# PR2387_Monitor.net
KiCad netlist of a schematic drawn in Altium Designer
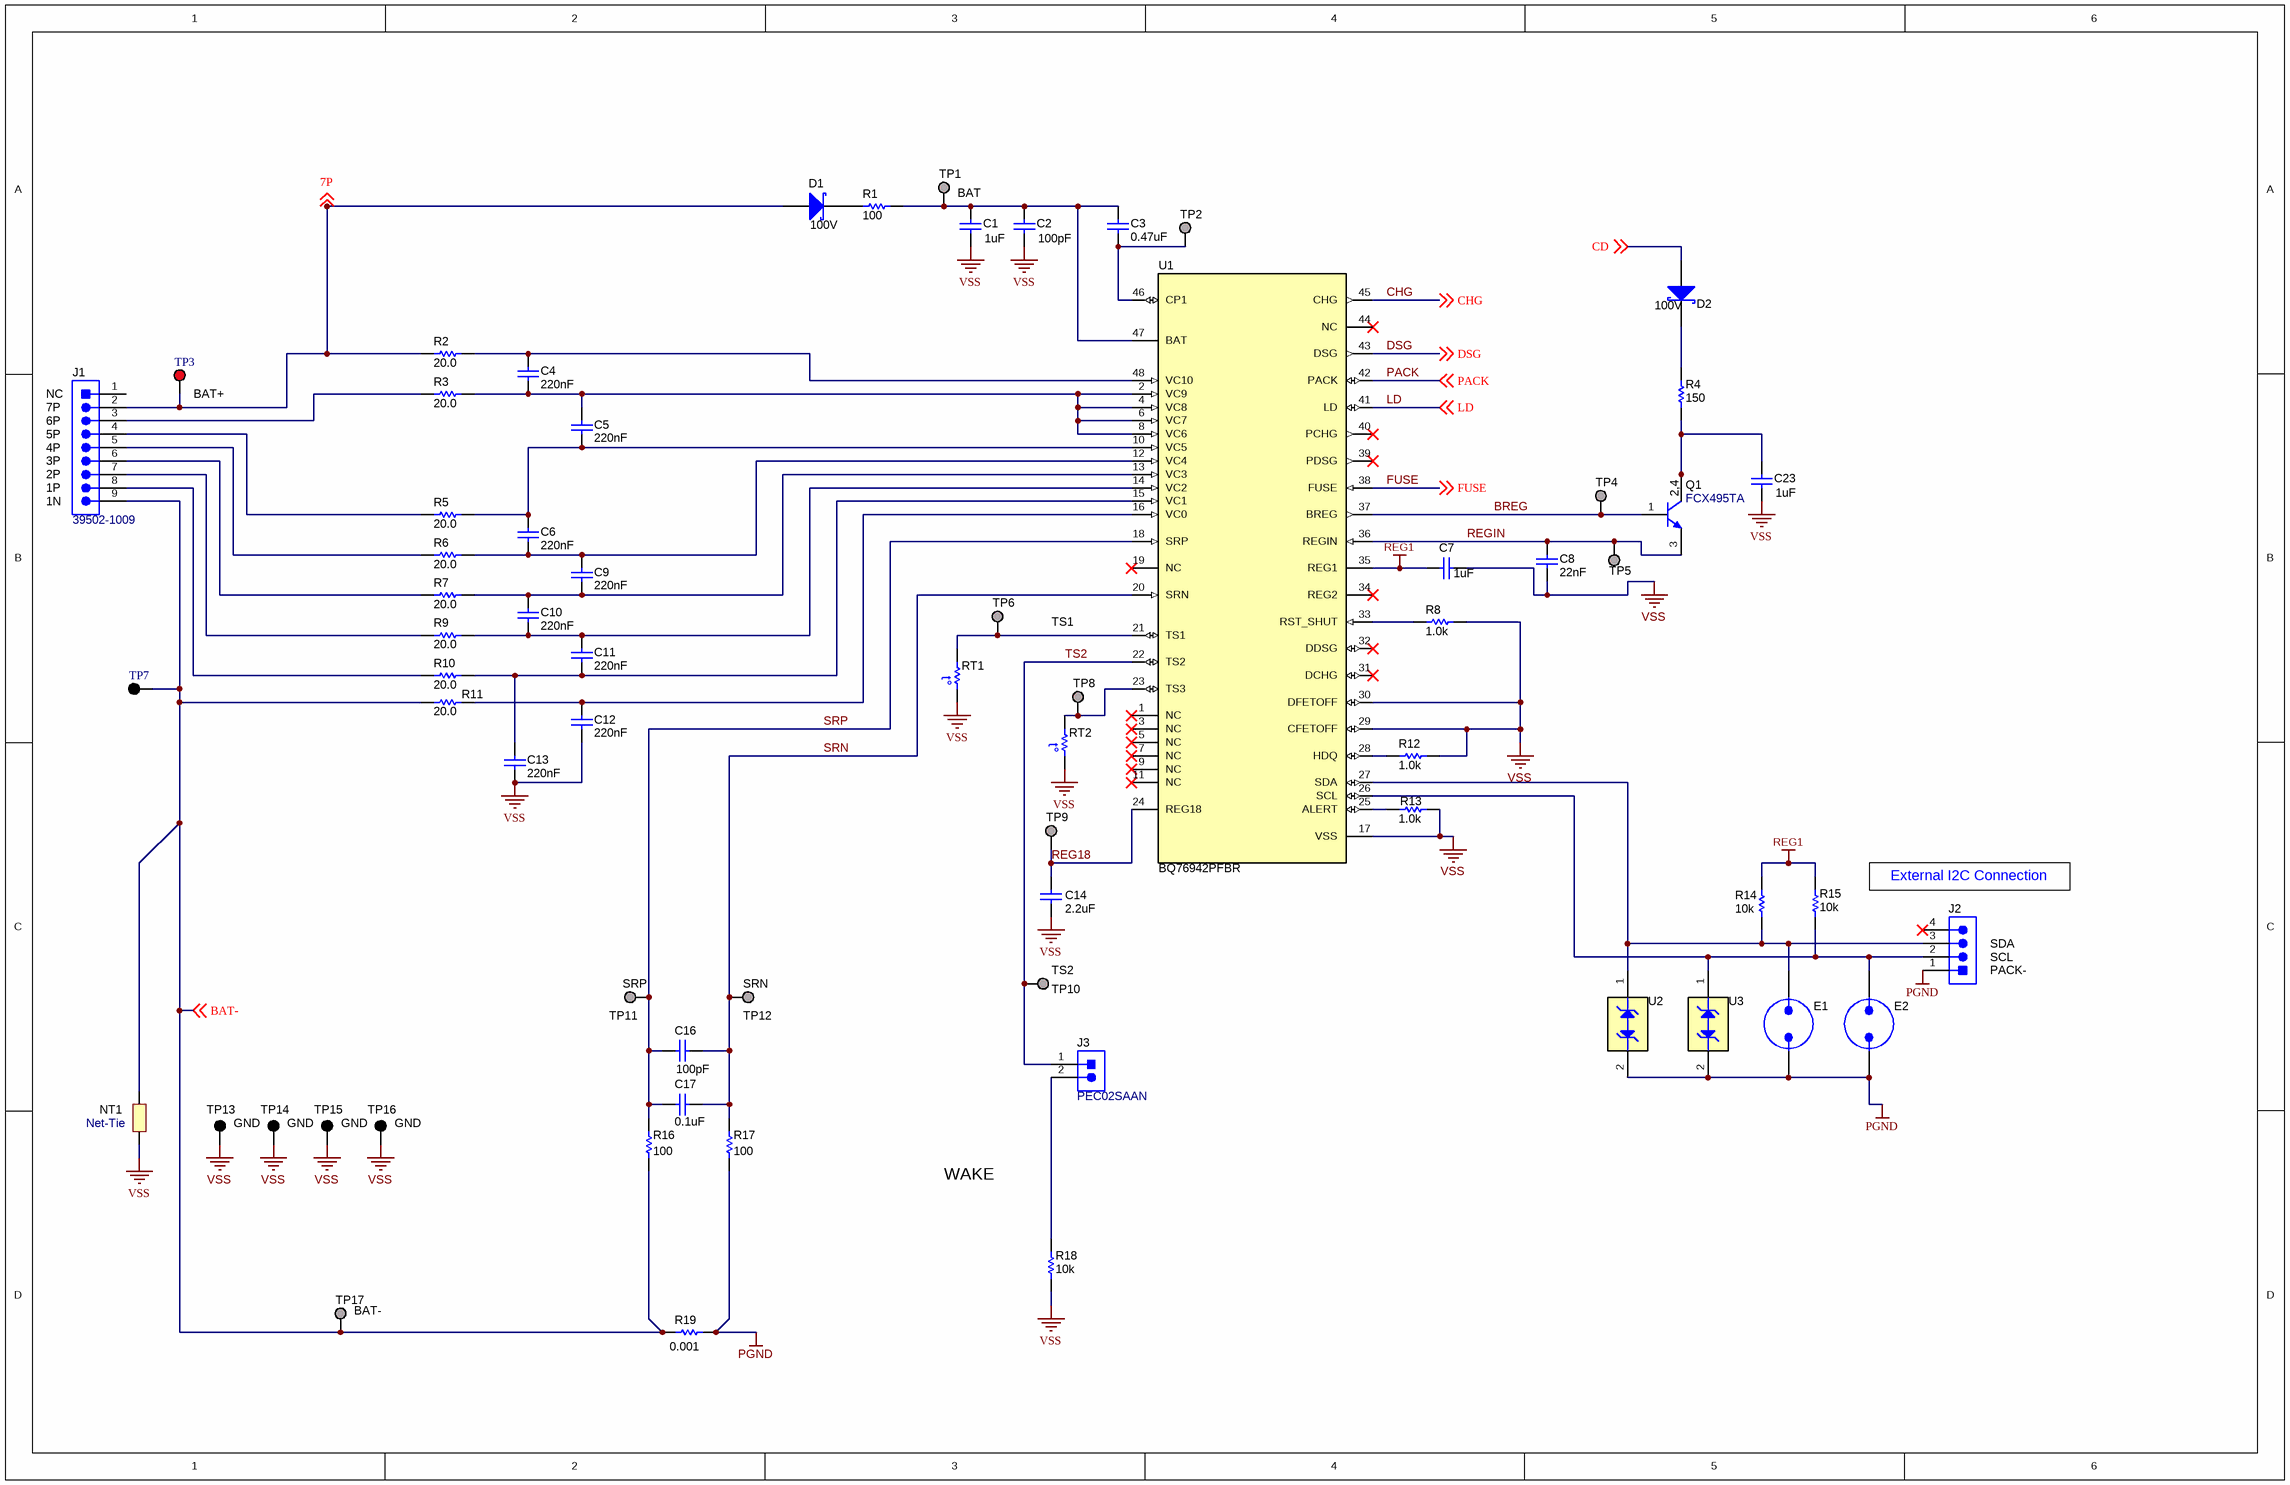
[diagram p0: PR2387_Monitor.SchDoc]

(export (version "E")
  (design (tool "Eeschema 10.0.6"))
  (components
    (comp (ref "C1")
      (value "C3216X7R2A105K160AA")
      (footprint "1206_180")
      (description "CAP, CERM, 1 uF, 100 V, +/- 10%, X7R, 1206")
      (fields
        (field (name "MANUFACTURER") "TDK")
        (field (name "VALUEDISPLAYED") "1uF")
        (field (name "PUBLISHER") "Texas Instruments")
      )
      (libsource (lib "Altium Vault - TI") (part "Capacitor"))
    )
    (comp (ref "C2")
      (value "GCM1885C2A101JA16D")
      (footprint "0603")
      (description "CAP, CERM, 100 pF, 100 V, +/- 5%, C0G/NP0, AEC-Q200 Grade 1, 0603")
      (fields
        (field (name "MANUFACTURER") "MuRata")
        (field (name "VALUEDISPLAYED") "100pF")
        (field (name "PUBLISHER") "Texas Instruments")
      )
      (libsource (lib "Altium Vault - TI") (part "Capacitor"))
    )
    (comp (ref "C3")
      (value "GCM219R71E474KA55D")
      (footprint "0805_HV")
      (description "CAP, CERM, 0.47 uF, 25 V, +/- 10%, X7R, AEC-Q200 Grade 1, 0805")
      (fields
        (field (name "MANUFACTURER") "MuRata")
        (field (name "VALUEDISPLAYED") "0.47uF")
        (field (name "PUBLISHER") "Texas Instruments")
      )
      (libsource (lib "Altium Vault - TI") (part "Capacitor"))
    )
    (comp (ref "C4")
      (value "C1608X7R1H224K080AB")
      (footprint "0603")
      (description "CAP, CERM, 0.22 uF, 50 V, +/- 10%, X7R, 0603")
      (fields
        (field (name "MANUFACTURER") "TDK")
        (field (name "CAP_F") "220nF")
        (field (name "PUBLISHER") "Texas Instruments")
      )
      (libsource (lib "Altium Vault - TI") (part "Capacitor"))
    )
    (comp (ref "C5")
      (value "C1608X7R1H224K080AB")
      (footprint "0603")
      (description "CAP, CERM, 0.22 uF, 50 V, +/- 10%, X7R, 0603")
      (fields
        (field (name "MANUFACTURER") "TDK")
        (field (name "CAP_F") "220nF")
        (field (name "PUBLISHER") "Texas Instruments")
      )
      (libsource (lib "Altium Vault - TI") (part "Capacitor"))
    )
    (comp (ref "C6")
      (value "C1608X7R1H224K080AB")
      (footprint "0603")
      (description "CAP, CERM, 0.22 uF, 50 V, +/- 10%, X7R, 0603")
      (fields
        (field (name "MANUFACTURER") "TDK")
        (field (name "CAP_F") "220nF")
        (field (name "PUBLISHER") "Texas Instruments")
      )
      (libsource (lib "Altium Vault - TI") (part "Capacitor"))
    )
    (comp (ref "C7")
      (value "EMK212B7105KG-T")
      (footprint "0805_HV")
      (description "CAP, CERM, 1 uF, 16 V, +/- 10%, X7R, 0805")
      (fields
        (field (name "MANUFACTURER") "Taiyo Yuden")
        (field (name "VALUEDISPLAYED") "1uF")
        (field (name "PUBLISHER") "Texas Instruments")
      )
      (libsource (lib "Altium Vault - TI") (part "Capacitor"))
    )
    (comp (ref "C8")
      (value "C0603C223K4RACTU")
      (footprint "0603")
      (description "CAP, CERM, 0.022 uF, 16 V, +/- 10%, X7R, 0603")
      (fields
        (field (name "MANUFACTURER") "Kemet")
        (field (name "CAP_F") "22nF")
        (field (name "PUBLISHER") "Texas Instruments")
      )
      (libsource (lib "Altium Vault - TI") (part "Capacitor"))
    )
    (comp (ref "C9")
      (value "C1608X7R1H224K080AB")
      (footprint "0603")
      (description "CAP, CERM, 0.22 uF, 50 V, +/- 10%, X7R, 0603")
      (fields
        (field (name "MANUFACTURER") "TDK")
        (field (name "CAP_F") "220nF")
        (field (name "PUBLISHER") "Texas Instruments")
      )
      (libsource (lib "Altium Vault - TI") (part "Capacitor"))
    )
    (comp (ref "C10")
      (value "C1608X7R1H224K080AB")
      (footprint "0603")
      (description "CAP, CERM, 0.22 uF, 50 V, +/- 10%, X7R, 0603")
      (fields
        (field (name "MANUFACTURER") "TDK")
        (field (name "CAP_F") "220nF")
        (field (name "PUBLISHER") "Texas Instruments")
      )
      (libsource (lib "Altium Vault - TI") (part "Capacitor"))
    )
    (comp (ref "C11")
      (value "C1608X7R1H224K080AB")
      (footprint "0603")
      (description "CAP, CERM, 0.22 uF, 50 V, +/- 10%, X7R, 0603")
      (fields
        (field (name "MANUFACTURER") "TDK")
        (field (name "CAP_F") "220nF")
        (field (name "PUBLISHER") "Texas Instruments")
      )
      (libsource (lib "Altium Vault - TI") (part "Capacitor"))
    )
    (comp (ref "C12")
      (value "C1608X7R1H224K080AB")
      (footprint "0603")
      (description "CAP, CERM, 0.22 uF, 50 V, +/- 10%, X7R, 0603")
      (fields
        (field (name "MANUFACTURER") "TDK")
        (field (name "CAP_F") "220nF")
        (field (name "PUBLISHER") "Texas Instruments")
      )
      (libsource (lib "Altium Vault - TI") (part "Capacitor"))
    )
    (comp (ref "C13")
      (value "C1608X7R1H224K080AB")
      (footprint "0603")
      (description "CAP, CERM, 0.22 uF, 50 V, +/- 10%, X7R, 0603")
      (fields
        (field (name "MANUFACTURER") "TDK")
        (field (name "CAP_F") "220nF")
        (field (name "PUBLISHER") "Texas Instruments")
      )
      (libsource (lib "Altium Vault - TI") (part "Capacitor"))
    )
    (comp (ref "C14")
      (value "EMK212B7225KG-T")
      (footprint "0805_HV")
      (description "CAP, CERM, 2.2 uF, 16 V, +/- 10%, X7R, 0805")
      (fields
        (field (name "MANUFACTURER") "Taiyo Yuden")
        (field (name "VALUEDISPLAYED") "2.2uF")
        (field (name "PUBLISHER") "Texas Instruments")
      )
      (libsource (lib "Altium Vault - TI") (part "Capacitor"))
    )
    (comp (ref "C16")
      (value "C0603C101J5GACTU")
      (footprint "0603")
      (description "CAP, CERM, 100 pF, 50 V, +/- 5%, C0G/NP0, 0603")
      (fields
        (field (name "MANUFACTURER") "Kemet")
        (field (name "VALUEDISPLAYED") "100pF")
        (field (name "PUBLISHER") "Texas Instruments")
      )
      (libsource (lib "Altium Vault - TI") (part "Capacitor"))
    )
    (comp (ref "C17")
      (value "885012206095")
      (footprint "0603")
      (description "CAP, CERM, 0.1 uF, 50 V, +/- 10%, X7R, 0603")
      (fields
        (field (name "MANUFACTURER") "Wurth Elektronik")
        (field (name "VALUEDISPLAYED") "0.1uF")
        (field (name "PUBLISHER") "Texas Instruments")
      )
      (libsource (lib "Altium Vault - TI") (part "Capacitor"))
    )
    (comp (ref "C23")
      (value "C3216X7R2A105K160AA")
      (footprint "1206_180")
      (description "CAP, CERM, 1 uF, 100 V, +/- 10%, X7R, 1206")
      (fields
        (field (name "MANUFACTURER") "TDK")
        (field (name "VALUEDISPLAYED") "1uF")
        (field (name "PUBLISHER") "Texas Instruments")
      )
      (libsource (lib "Altium Vault - TI") (part "Capacitor"))
    )
    (comp (ref "D1")
      (value "100V")
      (footprint "SOD-123")
      (description "Diode, Schottky, 100 V, 0.15 A, SOD-123")
      (fields (field (name "MANUFACTURER") "Diodes Inc.") (field (name "PARTNUMBER") "BAT46W-7-F"))
      (libsource (lib "Altium Vault - TI") (part "DIODE_SCHOTTKY"))
    )
    (comp (ref "D2")
      (value "100V")
      (footprint "SOD-123")
      (description "Diode, Schottky, 100 V, 0.15 A, SOD-123")
      (fields (field (name "MANUFACTURER") "Diodes Inc.") (field (name "PARTNUMBER") "BAT46W-7-F"))
      (libsource (lib "Altium Vault - TI") (part "DIODE_SCHOTTKY"))
    )
    (comp (ref "E1")
      (value "Spark Gap")
      (footprint "SPARK_GAP2")
      (libsource (lib "Altium Vault - TI") (part "CMP-0079939-1"))
    )
    (comp (ref "E2")
      (value "Spark Gap")
      (footprint "SPARK_GAP2")
      (libsource (lib "Altium Vault - TI") (part "CMP-0079939-1"))
    )
    (comp (ref "J1")
      (value "39502-1009")
      (footprint "Molex_39502-1009")
      (description "Header(Shrouded), 3.5mm, 9x1, R/A, TH")
      (fields (field (name "MANUFACTURER") "Molex") (field (name "PUBLISHER") "Texas Instruments"))
      (libsource (lib "Altium Vault - TI") (part "Header_9x1"))
    )
    (comp (ref "J2")
      (value "22/05/3041")
      (footprint "CONN_22-05-3041")
      (description "Header (friction lock), 100mil, 4x1, R/A, TH")
      (fields (field (name "MANUFACTURER") "Molex") (field (name "PUBLISHER") "Texas Instruments"))
      (libsource (lib "Altium Vault - TI") (part "CMP-0055187-1"))
    )
    (comp (ref "J3")
      (value "PEC02SAAN")
      (footprint "CONN_PEC02SAAN")
      (description "Header, 100mil, 2x1, Tin, TH")
      (fields
        (field (name "MANUFACTURER") "Sullins Connector Solutions")
        (field (name "PUBLISHER") "Texas Instruments")
      )
      (libsource (lib "Altium Vault - TI") (part "Header_2x1"))
    )
    (comp (ref "NT1")
      (value "Net-Tie")
      (footprint "Net-Tie_10milWide_30milLong")
      (description "Single point connection between nets.")
      (libsource (lib "Altium Vault - TI") (part "Net-Tie"))
    )
    (comp (ref "Q1")
      (value "FCX495TA")
      (footprint "SOT-89-3")
      (description "Transistor, NPN, 150 V, 1 A, AEC-Q101, SOT-89")
      (fields (field (name "MANUFACTURER") "Diodes Inc.") (field (name "PUBLISHER") "Texas Instruments"))
      (libsource (lib "Altium Vault - TI") (part "BJT_NPN_C24B1E3"))
    )
    (comp (ref "R1")
      (value "Resistor")
      (footprint "0603")
      (description "RES, 100, 5%, 0.1 W, AEC-Q200 Grade 0, 0603")
      (fields
        (field (name "PARTNUMBER") "CRCW0603100RJNEA")
        (field (name "MANUFACTURER") "Vishay-Dale")
        (field (name "VALUEDISPLAYED") "100")
        (field (name "PUBLISHER") "Texas Instruments")
      )
      (libsource (lib "Altium Vault - TI") (part "Resistor"))
    )
    (comp (ref "R2")
      (value "CRCW120620R0FKEA")
      (footprint "1206")
      (description "RES, 20.0, 1%, 0.25 W, AEC-Q200 Grade 0, 1206")
      (fields (field (name "MANUFACTURER") "Vishay-Dale") (field (name "VALUEDISPLAYED") "20.0"))
      (libsource (lib "Altium Vault - TI") (part "Resistor"))
    )
    (comp (ref "R3")
      (value "CRCW120620R0FKEA")
      (footprint "1206")
      (description "RES, 20.0, 1%, 0.25 W, AEC-Q200 Grade 0, 1206")
      (fields (field (name "MANUFACTURER") "Vishay-Dale") (field (name "VALUEDISPLAYED") "20.0"))
      (libsource (lib "Altium Vault - TI") (part "Resistor"))
    )
    (comp (ref "R4")
      (value "CRCW2512150RJNEG")
      (footprint "2512")
      (description "RES, 150, 5%, 1 W, AEC-Q200 Grade 0, 2512")
      (fields (field (name "MANUFACTURER") "Vishay-Dale") (field (name "VALUEDISPLAYED") "150"))
      (libsource (lib "Altium Vault - TI") (part "Resistor"))
    )
    (comp (ref "R5")
      (value "CRCW120620R0FKEA")
      (footprint "1206")
      (description "RES, 20.0, 1%, 0.25 W, AEC-Q200 Grade 0, 1206")
      (fields (field (name "MANUFACTURER") "Vishay-Dale") (field (name "VALUEDISPLAYED") "20.0"))
      (libsource (lib "Altium Vault - TI") (part "Resistor"))
    )
    (comp (ref "R6")
      (value "CRCW120620R0FKEA")
      (footprint "1206")
      (description "RES, 20.0, 1%, 0.25 W, AEC-Q200 Grade 0, 1206")
      (fields (field (name "MANUFACTURER") "Vishay-Dale") (field (name "VALUEDISPLAYED") "20.0"))
      (libsource (lib "Altium Vault - TI") (part "Resistor"))
    )
    (comp (ref "R7")
      (value "CRCW120620R0FKEA")
      (footprint "1206")
      (description "RES, 20.0, 1%, 0.25 W, AEC-Q200 Grade 0, 1206")
      (fields (field (name "MANUFACTURER") "Vishay-Dale") (field (name "VALUEDISPLAYED") "20.0"))
      (libsource (lib "Altium Vault - TI") (part "Resistor"))
    )
    (comp (ref "R8")
      (value "CRCW06031K00JNEA")
      (footprint "0603")
      (description "RES, 1.0 k, 5%, 0.1 W, AEC-Q200 Grade 0, 0603")
      (fields (field (name "MANUFACTURER") "Vishay-Dale") (field (name "VALUEDISPLAYED") "1.0k"))
      (libsource (lib "Altium Vault - TI") (part "Resistor"))
    )
    (comp (ref "R9")
      (value "CRCW120620R0FKEA")
      (footprint "1206")
      (description "RES, 20.0, 1%, 0.25 W, AEC-Q200 Grade 0, 1206")
      (fields (field (name "MANUFACTURER") "Vishay-Dale") (field (name "VALUEDISPLAYED") "20.0"))
      (libsource (lib "Altium Vault - TI") (part "Resistor"))
    )
    (comp (ref "R10")
      (value "CRCW120620R0FKEA")
      (footprint "1206")
      (description "RES, 20.0, 1%, 0.25 W, AEC-Q200 Grade 0, 1206")
      (fields (field (name "MANUFACTURER") "Vishay-Dale") (field (name "VALUEDISPLAYED") "20.0"))
      (libsource (lib "Altium Vault - TI") (part "Resistor"))
    )
    (comp (ref "R11")
      (value "CRCW120620R0FKEA")
      (footprint "1206")
      (description "RES, 20.0, 1%, 0.25 W, AEC-Q200 Grade 0, 1206")
      (fields (field (name "MANUFACTURER") "Vishay-Dale") (field (name "VALUEDISPLAYED") "20.0"))
      (libsource (lib "Altium Vault - TI") (part "Resistor"))
    )
    (comp (ref "R12")
      (value "CRCW06031K00JNEA")
      (footprint "0603")
      (description "RES, 1.0 k, 5%, 0.1 W, AEC-Q200 Grade 0, 0603")
      (fields (field (name "MANUFACTURER") "Vishay-Dale") (field (name "VALUEDISPLAYED") "1.0k"))
      (libsource (lib "Altium Vault - TI") (part "Resistor"))
    )
    (comp (ref "R13")
      (value "CRCW06031K00JNEA")
      (footprint "0603")
      (description "RES, 1.0 k, 5%, 0.1 W, AEC-Q200 Grade 0, 0603")
      (fields (field (name "MANUFACTURER") "Vishay-Dale") (field (name "VALUEDISPLAYED") "1.0k"))
      (libsource (lib "Altium Vault - TI") (part "Resistor"))
    )
    (comp (ref "R14")
      (value "CRCW060310K0JNEA")
      (footprint "0603")
      (description "RES, 10 k, 5%, 0.1 W, AEC-Q200 Grade 0, 0603")
      (fields (field (name "MANUFACTURER") "Vishay-Dale") (field (name "VALUEDISPLAYED") "10k"))
      (libsource (lib "Altium Vault - TI") (part "Resistor"))
    )
    (comp (ref "R15")
      (value "CRCW060310K0JNEA")
      (footprint "0603")
      (description "RES, 10 k, 5%, 0.1 W, AEC-Q200 Grade 0, 0603")
      (fields (field (name "MANUFACTURER") "Vishay-Dale") (field (name "VALUEDISPLAYED") "10k"))
      (libsource (lib "Altium Vault - TI") (part "CMP-0025701-4"))
    )
    (comp (ref "R16")
      (value "Resistor")
      (footprint "0603")
      (description "RES, 100, 5%, 0.1 W, AEC-Q200 Grade 0, 0603")
      (fields
        (field (name "PARTNUMBER") "CRCW0603100RJNEA")
        (field (name "MANUFACTURER") "Vishay-Dale")
        (field (name "VALUEDISPLAYED") "100")
        (field (name "PUBLISHER") "Texas Instruments")
      )
      (libsource (lib "Altium Vault - TI") (part "Resistor"))
    )
    (comp (ref "R17")
      (value "Resistor")
      (footprint "0603")
      (description "RES, 100, 5%, 0.1 W, AEC-Q200 Grade 0, 0603")
      (fields
        (field (name "PARTNUMBER") "CRCW0603100RJNEA")
        (field (name "MANUFACTURER") "Vishay-Dale")
        (field (name "VALUEDISPLAYED") "100")
        (field (name "PUBLISHER") "Texas Instruments")
      )
      (libsource (lib "Altium Vault - TI") (part "Resistor"))
    )
    (comp (ref "R18")
      (value "CRCW060310K0JNEA")
      (footprint "0603")
      (description "RES, 10 k, 5%, 0.1 W, AEC-Q200 Grade 0, 0603")
      (fields (field (name "MANUFACTURER") "Vishay-Dale") (field (name "VALUEDISPLAYED") "10k"))
      (libsource (lib "Altium Vault - TI") (part "Resistor"))
    )
    (comp (ref "R19")
      (value "Resistor")
      (footprint "1210M")
      (description "RES, 0.001, 1%, 1 W, 1210")
      (fields
        (field (name "PARTNUMBER") "PMR25HZPFV1L00")
        (field (name "MANUFACTURER") "Rohm")
        (field (name "VALUEDISPLAYED") "0.001")
        (field (name "PUBLISHER") "Texas Instruments")
      )
      (libsource (lib "Altium Vault - TI") (part "Resistor"))
    )
    (comp (ref "RT1")
      (value "Thermistor")
      (footprint "THERMISTOR_103AT-2")
      (description "Thermistor NTC, 10.0k ohm, 1%, Disc, 5x8.4 mm")
      (fields
        (field (name "PARTNUMBER") "103AT-2")
        (field (name "MANUFACTURER") "SEMITEC Corporation")
        (field (name "PUBLISHER") "Texas Instruments")
      )
      (libsource (lib "Altium Vault - TI") (part "Thermistor"))
    )
    (comp (ref "RT2")
      (value "Thermistor")
      (footprint "THERMISTOR_103AT-2")
      (description "Thermistor NTC, 10.0k ohm, 1%, Disc, 5x8.4 mm")
      (fields
        (field (name "PARTNUMBER") "103AT-2")
        (field (name "MANUFACTURER") "SEMITEC Corporation")
        (field (name "PUBLISHER") "Texas Instruments")
      )
      (libsource (lib "Altium Vault - TI") (part "Thermistor"))
    )
    (comp (ref "TP1")
      (value "TESTPOINT")
      (footprint "TP_VIA_060RND040")
      (description "TEST POINT.  No entry in BOM.")
      (libsource (lib "Altium Vault - TI") (part "TESTPOINT"))
    )
    (comp (ref "TP2")
      (value "TESTPOINT")
      (footprint "TP_VIA_060RND040")
      (description "TEST POINT.  No entry in BOM.")
      (libsource (lib "Altium Vault - TI") (part "TESTPOINT"))
    )
    (comp (ref "TP3")
      (value "TESTPOINT")
      (footprint "Keystone5010")
      (description "Test Point, Multipurpose, Red, TH")
      (fields
        (field (name "MANUFACTURER") "Keystone")
        (field (name "PARTNUMBER") "5010")
        (field (name "PUBLISHER") "Texas Instruments")
      )
      (libsource (lib "Altium Vault - TI") (part "5010"))
    )
    (comp (ref "TP4")
      (value "TESTPOINT")
      (footprint "TP_VIA_060RND040")
      (description "TEST POINT.  No entry in BOM.")
      (libsource (lib "Altium Vault - TI") (part "TESTPOINT"))
    )
    (comp (ref "TP5")
      (value "TESTPOINT")
      (footprint "TP_VIA_060RND040")
      (description "TEST POINT.  No entry in BOM.")
      (libsource (lib "Altium Vault - TI") (part "TESTPOINT"))
    )
    (comp (ref "TP6")
      (value "TESTPOINT")
      (footprint "TP_VIA_060RND040")
      (description "TEST POINT.  No entry in BOM.")
      (libsource (lib "Altium Vault - TI") (part "TESTPOINT"))
    )
    (comp (ref "TP7")
      (value "TESTPOINT")
      (footprint "Keystone5011")
      (description "Test Point, Multipurpose, Black, TH")
      (fields
        (field (name "MANUFACTURER") "Keystone")
        (field (name "PARTNUMBER") "5011")
        (field (name "PUBLISHER") "Texas Instruments")
      )
      (libsource (lib "Altium Vault - TI") (part "5011"))
    )
    (comp (ref "TP8")
      (value "TESTPOINT")
      (footprint "TP_VIA_060RND040")
      (description "TEST POINT.  No entry in BOM.")
      (libsource (lib "Altium Vault - TI") (part "TESTPOINT"))
    )
    (comp (ref "TP9")
      (value "TESTPOINT")
      (footprint "TP_VIA_060RND040")
      (description "TEST POINT.  No entry in BOM.")
      (libsource (lib "Altium Vault - TI") (part "TESTPOINT"))
    )
    (comp (ref "TP10")
      (value "TESTPOINT")
      (footprint "TP_VIA_060RND040")
      (description "TEST POINT.  No entry in BOM.")
      (libsource (lib "Altium Vault - TI") (part "TESTPOINT"))
    )
    (comp (ref "TP11")
      (value "TESTPOINT")
      (footprint "TP_VIA_060RND040")
      (description "TEST POINT.  No entry in BOM.")
      (libsource (lib "Altium Vault - TI") (part "TESTPOINT"))
    )
    (comp (ref "TP12")
      (value "TESTPOINT")
      (footprint "TP_VIA_060RND040")
      (description "TEST POINT.  No entry in BOM.")
      (libsource (lib "Altium Vault - TI") (part "TESTPOINT"))
    )
    (comp (ref "TP13")
      (value "5006")
      (footprint "Keystone5006")
      (description "Test Point, Compact, Black, TH")
      (fields (field (name "MANUFACTURER") "Keystone") (field (name "PUBLISHER") "Texas Instruments"))
      (libsource (lib "Altium Vault - TI") (part "5006"))
    )
    (comp (ref "TP14")
      (value "5006")
      (footprint "Keystone5006")
      (description "Test Point, Compact, Black, TH")
      (fields (field (name "MANUFACTURER") "Keystone") (field (name "PUBLISHER") "Texas Instruments"))
      (libsource (lib "Altium Vault - TI") (part "5006"))
    )
    (comp (ref "TP15")
      (value "5006")
      (footprint "Keystone5006")
      (description "Test Point, Compact, Black, TH")
      (fields (field (name "MANUFACTURER") "Keystone") (field (name "PUBLISHER") "Texas Instruments"))
      (libsource (lib "Altium Vault - TI") (part "5006"))
    )
    (comp (ref "TP16")
      (value "5006")
      (footprint "Keystone5006")
      (description "Test Point, Compact, Black, TH")
      (fields (field (name "MANUFACTURER") "Keystone") (field (name "PUBLISHER") "Texas Instruments"))
      (libsource (lib "Altium Vault - TI") (part "5006"))
    )
    (comp (ref "TP17")
      (value "TESTPOINT")
      (footprint "TP_VIA_060RND040")
      (description "TEST POINT.  No entry in BOM.")
      (libsource (lib "Altium Vault - TI") (part "TESTPOINT"))
    )
    (comp (ref "U1")
      (value "BQ76942PFBR")
      (footprint "PFB0048A_N")
      (description "Multicell Battery Monitor and Protection Family, PFB0048A (TQFP-48)")
      (fields
        (field (name "ALTERNATE PARTNUMBER") "BQ76942PFBT")
        (field (name "MANUFACTURER") "Texas Instruments")
        (field (name "PARTNUMBER") "BQ76942PFBR")
      )
      (libsource (lib "Altium Vault - TI") (part "bq76942"))
    )
    (comp (ref "U2")
      (value "TPD1E10B06DPYR")
      (footprint "DPY0002A")
      (description "Single-Channel ESD in 0402 Package With 10pF Capacitance and 6V Breakdown, DPY0002A (X1SON-2)")
      (fields
        (field (name "MANUFACTURER") "Texas Instruments")
        (field (name "ALTERNATE PARTNUMBER") "TPD1E10B06DPYT")
      )
      (libsource (lib "Altium Vault - TI") (part "TPD1E10B06"))
    )
    (comp (ref "U3")
      (value "TPD1E10B06DPYR")
      (footprint "DPY0002A")
      (description "Single-Channel ESD in 0402 Package With 10pF Capacitance and 6V Breakdown, DPY0002A (X1SON-2)")
      (fields
        (field (name "MANUFACTURER") "Texas Instruments")
        (field (name "ALTERNATE PARTNUMBER") "TPD1E10B06DPYT")
      )
      (libsource (lib "Altium Vault - TI") (part "TPD1E10B06"))
    )
  )
  (nets
    (net (code "1") (name "/BREG") (class "Default")
      (node (ref "Q1") (pin "1") (pinfunction "B_1") (pintype "passive"))
      (node (ref "TP4") (pin "1") (pintype "passive"))
      (node (ref "U1") (pin "37") (pinfunction "BREG_37") (pintype "output"))
    )
    (net (code "2") (name "/REG18") (class "Default")
      (node (ref "C14") (pin "2") (pinfunction "2_2") (pintype "passive"))
      (node (ref "TP9") (pin "1") (pintype "passive"))
      (node (ref "U1") (pin "24") (pinfunction "REG18_24") (pintype "power_in"))
    )
    (net (code "3") (name "/REGIN") (class "Default")
      (node (ref "C8") (pin "2") (pinfunction "2_2") (pintype "passive"))
      (node (ref "Q1") (pin "3") (pinfunction "E_3") (pintype "passive"))
      (node (ref "TP5") (pin "1") (pintype "passive"))
      (node (ref "U1") (pin "36") (pinfunction "REGIN_36") (pintype "input"))
    )
    (net (code "4") (name "/SRN") (class "Default")
      (node (ref "C16") (pin "1") (pinfunction "1_1") (pintype "passive"))
      (node (ref "C17") (pin "2") (pinfunction "2_2") (pintype "passive"))
      (node (ref "R17") (pin "2") (pinfunction "2_2") (pintype "passive"))
      (node (ref "TP12") (pin "1") (pintype "passive"))
      (node (ref "U1") (pin "20") (pinfunction "SRN_20") (pintype "input"))
    )
    (net (code "5") (name "/SRP") (class "Default")
      (node (ref "C16") (pin "2") (pinfunction "2_2") (pintype "passive"))
      (node (ref "C17") (pin "1") (pinfunction "1_1") (pintype "passive"))
      (node (ref "R16") (pin "2") (pinfunction "2_2") (pintype "passive"))
      (node (ref "TP11") (pin "1") (pintype "passive"))
      (node (ref "U1") (pin "18") (pinfunction "SRP_18") (pintype "input"))
    )
    (net (code "6") (name "/TS2") (class "Default")
      (node (ref "J3") (pin "1") (pinfunction "1_1") (pintype "passive"))
      (node (ref "TP10") (pin "1") (pintype "passive"))
      (node (ref "U1") (pin "22") (pinfunction "TS2_22") (pintype "bidirectional"))
    )
    (net (code "7") (name "7P") (class "Default")
      (node (ref "D1") (pin "2") (pinfunction "A_2") (pintype "passive"))
      (node (ref "J1") (pin "2") (pinfunction "2_2") (pintype "passive"))
      (node (ref "R2") (pin "1") (pinfunction "1_1") (pintype "passive"))
      (node (ref "TP3") (pin "1") (pintype "passive"))
    )
    (net (code "8") (name "BAT-") (class "Default")
      (node (ref "J1") (pin "9") (pinfunction "9_9") (pintype "passive"))
      (node (ref "NT1") (pin "2") (pinfunction "2_2") (pintype "passive"))
      (node (ref "R11") (pin "1") (pinfunction "1_1") (pintype "passive"))
      (node (ref "R16") (pin "1") (pinfunction "1_1") (pintype "passive"))
      (node (ref "R19") (pin "2") (pinfunction "2_2") (pintype "passive"))
      (node (ref "TP17") (pin "1") (pintype "passive"))
      (node (ref "TP7") (pin "1") (pintype "passive"))
    )
    (net (code "9") (name "CD") (class "Default")
      (node (ref "D2") (pin "2") (pinfunction "A_2") (pintype "passive"))
    )
    (net (code "10") (name "CHG") (class "Default")
      (node (ref "U1") (pin "45") (pinfunction "CHG_45") (pintype "output"))
    )
    (net (code "11") (name "DSG") (class "Default")
      (node (ref "U1") (pin "43") (pinfunction "DSG_43") (pintype "output"))
    )
    (net (code "12") (name "FUSE") (class "Default")
      (node (ref "U1") (pin "38") (pinfunction "FUSE_38") (pintype "input"))
    )
    (net (code "13") (name "LD") (class "Default")
      (node (ref "U1") (pin "41") (pinfunction "LD_41") (pintype "bidirectional"))
    )
    (net (code "14") (name "Net-(C23-Pad1)") (class "Default")
      (node (ref "C23") (pin "1") (pinfunction "1_1") (pintype "passive"))
      (node (ref "Q1") (pin "2") (pinfunction "C_2") (pintype "passive"))
      (node (ref "Q1") (pin "4") (pinfunction "C_4") (pintype "passive"))
      (node (ref "R4") (pin "1") (pinfunction "1_1") (pintype "passive"))
    )
    (net (code "15") (name "Net-(D1-K)") (class "Default")
      (node (ref "D1") (pin "1") (pinfunction "K_1") (pintype "passive"))
      (node (ref "R1") (pin "2") (pinfunction "2_2") (pintype "passive"))
    )
    (net (code "16") (name "Net-(D2-K)") (class "Default")
      (node (ref "D2") (pin "1") (pinfunction "K_1") (pintype "passive"))
      (node (ref "R4") (pin "2") (pinfunction "2_2") (pintype "passive"))
    )
    (net (code "17") (name "Net-(J1-Pad3)") (class "Default")
      (node (ref "J1") (pin "3") (pinfunction "3_3") (pintype "passive"))
      (node (ref "R3") (pin "1") (pinfunction "1_1") (pintype "passive"))
    )
    (net (code "18") (name "Net-(J1-Pad4)") (class "Default")
      (node (ref "J1") (pin "4") (pinfunction "4_4") (pintype "passive"))
      (node (ref "R5") (pin "1") (pinfunction "1_1") (pintype "passive"))
    )
    (net (code "19") (name "Net-(J1-Pad5)") (class "Default")
      (node (ref "J1") (pin "5") (pinfunction "5_5") (pintype "passive"))
      (node (ref "R6") (pin "1") (pinfunction "1_1") (pintype "passive"))
    )
    (net (code "20") (name "Net-(J1-Pad6)") (class "Default")
      (node (ref "J1") (pin "6") (pinfunction "6_6") (pintype "passive"))
      (node (ref "R7") (pin "1") (pinfunction "1_1") (pintype "passive"))
    )
    (net (code "21") (name "Net-(J1-Pad7)") (class "Default")
      (node (ref "J1") (pin "7") (pinfunction "7_7") (pintype "passive"))
      (node (ref "R9") (pin "1") (pinfunction "1_1") (pintype "passive"))
    )
    (net (code "22") (name "Net-(J1-Pad8)") (class "Default")
      (node (ref "J1") (pin "8") (pinfunction "8_8") (pintype "passive"))
      (node (ref "R10") (pin "1") (pinfunction "1_1") (pintype "passive"))
    )
    (net (code "23") (name "Net-(J3-Pad2)") (class "Default")
      (node (ref "J3") (pin "2") (pinfunction "2_2") (pintype "passive"))
      (node (ref "R18") (pin "2") (pinfunction "2_2") (pintype "passive"))
    )
    (net (code "24") (name "Net-(U1-ALERT)") (class "Default")
      (node (ref "R13") (pin "2") (pinfunction "2_2") (pintype "passive"))
      (node (ref "U1") (pin "25") (pinfunction "ALERT_25") (pintype "bidirectional"))
    )
    (net (code "25") (name "Net-(U1-BAT)") (class "Default")
      (node (ref "C1") (pin "1") (pinfunction "1_1") (pintype "passive"))
      (node (ref "C2") (pin "1") (pinfunction "1_1") (pintype "passive"))
      (node (ref "C3") (pin "1") (pinfunction "1_1") (pintype "passive"))
      (node (ref "R1") (pin "1") (pinfunction "1_1") (pintype "passive"))
      (node (ref "TP1") (pin "1") (pintype "passive"))
      (node (ref "U1") (pin "47") (pinfunction "BAT_47") (pintype "power_in"))
    )
    (net (code "26") (name "Net-(U1-CP1)") (class "Default")
      (node (ref "C3") (pin "2") (pinfunction "2_2") (pintype "passive"))
      (node (ref "TP2") (pin "1") (pintype "passive"))
      (node (ref "U1") (pin "46") (pinfunction "CP1_46") (pintype "bidirectional"))
    )
    (net (code "27") (name "Net-(U1-HDQ)") (class "Default")
      (node (ref "R12") (pin "2") (pinfunction "2_2") (pintype "passive"))
      (node (ref "U1") (pin "28") (pinfunction "HDQ_28") (pintype "bidirectional"))
    )
    (net (code "28") (name "Net-(U1-RST_SHUT)") (class "Default")
      (node (ref "R8") (pin "2") (pinfunction "2_2") (pintype "passive"))
      (node (ref "U1") (pin "33") (pinfunction "RST_SHUT_33") (pintype "input"))
    )
    (net (code "29") (name "Net-(U1-SCL)") (class "Default")
      (node (ref "E2") (pin "1") (pinfunction "1_1") (pintype "passive"))
      (node (ref "J2") (pin "2") (pinfunction "2_2") (pintype "passive"))
      (node (ref "R15") (pin "2") (pinfunction "2_2") (pintype "passive"))
      (node (ref "U1") (pin "26") (pinfunction "SCL_26") (pintype "bidirectional"))
      (node (ref "U3") (pin "1") (pinfunction "K_1") (pintype "passive"))
    )
    (net (code "30") (name "Net-(U1-SDA)") (class "Default")
      (node (ref "E1") (pin "1") (pinfunction "1_1") (pintype "passive"))
      (node (ref "J2") (pin "3") (pinfunction "3_3") (pintype "passive"))
      (node (ref "R14") (pin "2") (pinfunction "2_2") (pintype "passive"))
      (node (ref "U1") (pin "27") (pinfunction "SDA_27") (pintype "bidirectional"))
      (node (ref "U2") (pin "1") (pinfunction "K_1") (pintype "passive"))
    )
    (net (code "31") (name "Net-(U1-TS1)") (class "Default")
      (node (ref "RT1") (pin "1") (pinfunction "1_1") (pintype "passive"))
      (node (ref "TP6") (pin "1") (pintype "passive"))
      (node (ref "U1") (pin "21") (pinfunction "TS1_21") (pintype "bidirectional"))
    )
    (net (code "32") (name "Net-(U1-TS3)") (class "Default")
      (node (ref "RT2") (pin "1") (pinfunction "1_1") (pintype "passive"))
      (node (ref "TP8") (pin "1") (pintype "passive"))
      (node (ref "U1") (pin "23") (pinfunction "TS3_23") (pintype "bidirectional"))
    )
    (net (code "33") (name "Net-(U1-VC0)") (class "Default")
      (node (ref "C12") (pin "1") (pinfunction "1_1") (pintype "passive"))
      (node (ref "R11") (pin "2") (pinfunction "2_2") (pintype "passive"))
      (node (ref "U1") (pin "16") (pinfunction "VC0_16") (pintype "input"))
    )
    (net (code "34") (name "Net-(U1-VC1)") (class "Default")
      (node (ref "C11") (pin "2") (pinfunction "2_2") (pintype "passive"))
      (node (ref "C13") (pin "1") (pinfunction "1_1") (pintype "passive"))
      (node (ref "R10") (pin "2") (pinfunction "2_2") (pintype "passive"))
      (node (ref "U1") (pin "15") (pinfunction "VC1_15") (pintype "input"))
    )
    (net (code "35") (name "Net-(U1-VC2)") (class "Default")
      (node (ref "C10") (pin "2") (pinfunction "2_2") (pintype "passive"))
      (node (ref "C11") (pin "1") (pinfunction "1_1") (pintype "passive"))
      (node (ref "R9") (pin "2") (pinfunction "2_2") (pintype "passive"))
      (node (ref "U1") (pin "14") (pinfunction "VC2_14") (pintype "input"))
    )
    (net (code "36") (name "Net-(U1-VC3)") (class "Default")
      (node (ref "C10") (pin "1") (pinfunction "1_1") (pintype "passive"))
      (node (ref "C9") (pin "2") (pinfunction "2_2") (pintype "passive"))
      (node (ref "R7") (pin "2") (pinfunction "2_2") (pintype "passive"))
      (node (ref "U1") (pin "13") (pinfunction "VC3_13") (pintype "input"))
    )
    (net (code "37") (name "Net-(U1-VC4)") (class "Default")
      (node (ref "C6") (pin "2") (pinfunction "2_2") (pintype "passive"))
      (node (ref "C9") (pin "1") (pinfunction "1_1") (pintype "passive"))
      (node (ref "R6") (pin "2") (pinfunction "2_2") (pintype "passive"))
      (node (ref "U1") (pin "12") (pinfunction "VC4_12") (pintype "input"))
    )
    (net (code "38") (name "Net-(U1-VC5)") (class "Default")
      (node (ref "C5") (pin "2") (pinfunction "2_2") (pintype "passive"))
      (node (ref "C6") (pin "1") (pinfunction "1_1") (pintype "passive"))
      (node (ref "R5") (pin "2") (pinfunction "2_2") (pintype "passive"))
      (node (ref "U1") (pin "10") (pinfunction "VC5_10") (pintype "input"))
    )
    (net (code "39") (name "Net-(U1-VC6)") (class "Default")
      (node (ref "C4") (pin "2") (pinfunction "2_2") (pintype "passive"))
      (node (ref "C5") (pin "1") (pinfunction "1_1") (pintype "passive"))
      (node (ref "R3") (pin "2") (pinfunction "2_2") (pintype "passive"))
      (node (ref "U1") (pin "2") (pinfunction "VC9_2") (pintype "input"))
      (node (ref "U1") (pin "4") (pinfunction "VC8_4") (pintype "input"))
      (node (ref "U1") (pin "6") (pinfunction "VC7_6") (pintype "input"))
      (node (ref "U1") (pin "8") (pinfunction "VC6_8") (pintype "input"))
    )
    (net (code "40") (name "Net-(U1-VC10)") (class "Default")
      (node (ref "C4") (pin "1") (pinfunction "1_1") (pintype "passive"))
      (node (ref "R2") (pin "2") (pinfunction "2_2") (pintype "passive"))
      (node (ref "U1") (pin "48") (pinfunction "VC10_48") (pintype "input"))
    )
    (net (code "41") (name "PACK") (class "Default")
      (node (ref "U1") (pin "42") (pinfunction "PACK_42") (pintype "bidirectional"))
    )
    (net (code "42") (name "PGND") (class "Default")
      (node (ref "E1") (pin "2") (pinfunction "2_2") (pintype "passive"))
      (node (ref "E2") (pin "2") (pinfunction "2_2") (pintype "passive"))
      (node (ref "J2") (pin "1") (pinfunction "1_1") (pintype "passive"))
      (node (ref "R17") (pin "1") (pinfunction "1_1") (pintype "passive"))
      (node (ref "R19") (pin "1") (pinfunction "1_1") (pintype "passive"))
      (node (ref "U2") (pin "2") (pinfunction "A_2") (pintype "passive"))
      (node (ref "U3") (pin "2") (pinfunction "A_2") (pintype "passive"))
    )
    (net (code "43") (name "REG1") (class "Default")
      (node (ref "C7") (pin "2") (pinfunction "2_2") (pintype "passive"))
      (node (ref "R14") (pin "1") (pinfunction "1_1") (pintype "passive"))
      (node (ref "R15") (pin "1") (pinfunction "1_1") (pintype "passive"))
      (node (ref "U1") (pin "35") (pinfunction "REG1_35") (pintype "power_in"))
    )
    (net (code "44") (name "VSS") (class "Default")
      (node (ref "C1") (pin "2") (pinfunction "2_2") (pintype "passive"))
      (node (ref "C12") (pin "2") (pinfunction "2_2") (pintype "passive"))
      (node (ref "C13") (pin "2") (pinfunction "2_2") (pintype "passive"))
      (node (ref "C14") (pin "1") (pinfunction "1_1") (pintype "passive"))
      (node (ref "C2") (pin "2") (pinfunction "2_2") (pintype "passive"))
      (node (ref "C23") (pin "2") (pinfunction "2_2") (pintype "passive"))
      (node (ref "C7") (pin "1") (pinfunction "1_1") (pintype "passive"))
      (node (ref "C8") (pin "1") (pinfunction "1_1") (pintype "passive"))
      (node (ref "NT1") (pin "1") (pinfunction "1_1") (pintype "passive"))
      (node (ref "R12") (pin "1") (pinfunction "1_1") (pintype "passive"))
      (node (ref "R13") (pin "1") (pinfunction "1_1") (pintype "passive"))
      (node (ref "R18") (pin "1") (pinfunction "1_1") (pintype "passive"))
      (node (ref "R8") (pin "1") (pinfunction "1_1") (pintype "passive"))
      (node (ref "RT1") (pin "2") (pinfunction "2_2") (pintype "passive"))
      (node (ref "RT2") (pin "2") (pinfunction "2_2") (pintype "passive"))
      (node (ref "TP13") (pin "1") (pintype "passive"))
      (node (ref "TP14") (pin "1") (pintype "passive"))
      (node (ref "TP15") (pin "1") (pintype "passive"))
      (node (ref "TP16") (pin "1") (pintype "passive"))
      (node (ref "U1") (pin "17") (pinfunction "VSS_17") (pintype "power_in"))
      (node (ref "U1") (pin "29") (pinfunction "CFETOFF_29") (pintype "bidirectional"))
      (node (ref "U1") (pin "30") (pinfunction "DFETOFF_30") (pintype "bidirectional"))
    )
    (net (code "45") (name "unconnected-(J1-Pad1)") (class "Default")
      (node (ref "J1") (pin "1") (pinfunction "1_1") (pintype "passive"))
    )
    (net (code "46") (name "unconnected-(J2-Pad4)") (class "Default")
      (node (ref "J2") (pin "4") (pinfunction "4_4") (pintype "passive+no_connect"))
    )
    (net (code "47") (name "unconnected-(U1-DCHG-Pad31)") (class "Default")
      (node (ref "U1") (pin "31") (pinfunction "DCHG_31") (pintype "bidirectional+no_connect"))
    )
    (net (code "48") (name "unconnected-(U1-DDSG-Pad32)") (class "Default")
      (node (ref "U1") (pin "32") (pinfunction "DDSG_32") (pintype "bidirectional+no_connect"))
    )
    (net (code "49") (name "unconnected-(U1-NC-Pad1)") (class "Default")
      (node (ref "U1") (pin "1") (pinfunction "NC_1") (pintype "passive+no_connect"))
    )
    (net (code "50") (name "unconnected-(U1-NC-Pad3)") (class "Default")
      (node (ref "U1") (pin "3") (pinfunction "NC_3") (pintype "passive+no_connect"))
    )
    (net (code "51") (name "unconnected-(U1-NC-Pad5)") (class "Default")
      (node (ref "U1") (pin "5") (pinfunction "NC_5") (pintype "passive+no_connect"))
    )
    (net (code "52") (name "unconnected-(U1-NC-Pad7)") (class "Default")
      (node (ref "U1") (pin "7") (pinfunction "NC_7") (pintype "passive+no_connect"))
    )
    (net (code "53") (name "unconnected-(U1-NC-Pad9)") (class "Default")
      (node (ref "U1") (pin "9") (pinfunction "NC_9") (pintype "passive+no_connect"))
    )
    (net (code "54") (name "unconnected-(U1-NC-Pad11)") (class "Default")
      (node (ref "U1") (pin "11") (pinfunction "NC_11") (pintype "passive+no_connect"))
    )
    (net (code "55") (name "unconnected-(U1-NC-Pad19)") (class "Default")
      (node (ref "U1") (pin "19") (pinfunction "NC_19") (pintype "passive+no_connect"))
    )
    (net (code "56") (name "unconnected-(U1-NC-Pad44)") (class "Default")
      (node (ref "U1") (pin "44") (pinfunction "NC_44") (pintype "passive+no_connect"))
    )
    (net (code "57") (name "unconnected-(U1-PCHG-Pad40)") (class "Default")
      (node (ref "U1") (pin "40") (pinfunction "PCHG_40") (pintype "output+no_connect"))
    )
    (net (code "58") (name "unconnected-(U1-PDSG-Pad39)") (class "Default")
      (node (ref "U1") (pin "39") (pinfunction "PDSG_39") (pintype "output+no_connect"))
    )
    (net (code "59") (name "unconnected-(U1-REG2-Pad34)") (class "Default")
      (node (ref "U1") (pin "34") (pinfunction "REG2_34") (pintype "power_in+no_connect"))
    )
  )
)
